# e3_ej5_esquematico.net
KiCad netlist of a schematic drawn in Altium Designer
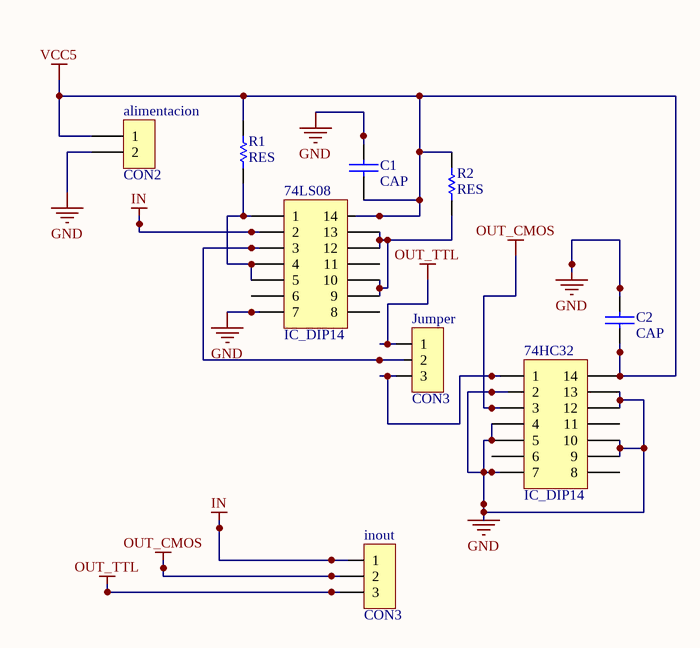
[diagram p0: e3_ej5_esquematico.SchDoc]

(export (version "E")
  (design (tool "Eeschema 10.0.6"))
  (components
    (comp (ref "74HC32") (value "IC_DIP14") (footprint "DIP14") (libsource (lib "LIBEBAL") (part "IC_DIP14")))
    (comp (ref "74LS08") (value "IC_DIP14") (footprint "DIP14") (libsource (lib "LIBEBAL") (part "IC_DIP14")))
    (comp (ref "alimentacion") (value "CON2") (footprint "SIP2") (libsource (lib "LIBEBAL") (part "CON2")))
    (comp (ref "C1") (value "CAP") (footprint "CAP200") (libsource (lib "LIBEBAL") (part "CAP")))
    (comp (ref "C2") (value "CAP") (footprint "CAP200") (libsource (lib "LIBEBAL") (part "CAP")))
    (comp (ref "inout") (value "CON3") (footprint "SIP3") (libsource (lib "LIBEBAL") (part "CON3")))
    (comp (ref "Jumper") (value "CON3") (footprint "SIP3") (libsource (lib "LIBEBAL") (part "CON3")))
    (comp (ref "R1") (value "RES") (footprint "RES300") (libsource (lib "LIBEBAL") (part "RES")))
    (comp (ref "R2") (value "RES") (footprint "RES300") (libsource (lib "LIBEBAL") (part "RES")))
  )
  (nets
    (net (code "1") (name "GND") (class "Default")
      (node (ref "74HC32") (pin "10") (pinfunction "10_10") (pintype "passive"))
      (node (ref "74HC32") (pin "12") (pinfunction "12_12") (pintype "passive"))
      (node (ref "74HC32") (pin "13") (pinfunction "13_13") (pintype "passive"))
      (node (ref "74HC32") (pin "2") (pinfunction "2_2") (pintype "passive"))
      (node (ref "74HC32") (pin "4") (pinfunction "4_4") (pintype "passive"))
      (node (ref "74HC32") (pin "5") (pinfunction "5_5") (pintype "passive"))
      (node (ref "74HC32") (pin "7") (pinfunction "7_7") (pintype "passive"))
      (node (ref "74HC32") (pin "9") (pinfunction "9_9") (pintype "passive"))
      (node (ref "74LS08") (pin "7") (pinfunction "7_7") (pintype "passive"))
      (node (ref "C1") (pin "1") (pinfunction "1_1") (pintype "passive"))
      (node (ref "C2") (pin "1") (pinfunction "1_1") (pintype "passive"))
      (node (ref "alimentacion") (pin "2") (pinfunction "2_2") (pintype "passive"))
    )
    (net (code "2") (name "IN") (class "Default")
      (node (ref "74LS08") (pin "2") (pinfunction "2_2") (pintype "passive"))
      (node (ref "inout") (pin "1") (pinfunction "1_1") (pintype "passive"))
    )
    (net (code "3") (name "Net-(74HC32-Pad1)") (class "Default")
      (node (ref "74HC32") (pin "1") (pinfunction "1_1") (pintype "passive"))
      (node (ref "Jumper") (pin "3") (pinfunction "3_3") (pintype "passive"))
    )
    (net (code "4") (name "Net-(74LS08-Pad1)") (class "Default")
      (node (ref "74LS08") (pin "1") (pinfunction "1_1") (pintype "passive"))
      (node (ref "74LS08") (pin "4") (pinfunction "4_4") (pintype "passive"))
      (node (ref "74LS08") (pin "5") (pinfunction "5_5") (pintype "passive"))
      (node (ref "R1") (pin "1") (pinfunction "1_1") (pintype "passive"))
    )
    (net (code "5") (name "Net-(74LS08-Pad3)") (class "Default")
      (node (ref "74LS08") (pin "3") (pinfunction "3_3") (pintype "passive"))
      (node (ref "Jumper") (pin "2") (pinfunction "2_2") (pintype "passive"))
    )
    (net (code "6") (name "Net-(74LS08-Pad10)") (class "Default")
      (node (ref "74LS08") (pin "10") (pinfunction "10_10") (pintype "passive"))
      (node (ref "74LS08") (pin "12") (pinfunction "12_12") (pintype "passive"))
      (node (ref "74LS08") (pin "13") (pinfunction "13_13") (pintype "passive"))
      (node (ref "74LS08") (pin "9") (pinfunction "9_9") (pintype "passive"))
      (node (ref "R2") (pin "1") (pinfunction "1_1") (pintype "passive"))
    )
    (net (code "7") (name "OUT_CMOS") (class "Default")
      (node (ref "74HC32") (pin "3") (pinfunction "3_3") (pintype "passive"))
      (node (ref "inout") (pin "2") (pinfunction "2_2") (pintype "passive"))
    )
    (net (code "8") (name "OUT_TTL") (class "Default")
      (node (ref "Jumper") (pin "1") (pinfunction "1_1") (pintype "passive"))
      (node (ref "inout") (pin "3") (pinfunction "3_3") (pintype "passive"))
    )
    (net (code "9") (name "VCC5") (class "Default")
      (node (ref "74HC32") (pin "14") (pinfunction "14_14") (pintype "passive"))
      (node (ref "74LS08") (pin "14") (pinfunction "14_14") (pintype "passive"))
      (node (ref "C1") (pin "2") (pinfunction "2_2") (pintype "passive"))
      (node (ref "C2") (pin "2") (pinfunction "2_2") (pintype "passive"))
      (node (ref "R1") (pin "2") (pinfunction "2_2") (pintype "passive"))
      (node (ref "R2") (pin "2") (pinfunction "2_2") (pintype "passive"))
      (node (ref "alimentacion") (pin "1") (pinfunction "1_1") (pintype "passive"))
    )
    (net (code "10") (name "unconnected-(74HC32-Pad6)") (class "Default")
      (node (ref "74HC32") (pin "6") (pinfunction "6_6") (pintype "passive"))
    )
    (net (code "11") (name "unconnected-(74HC32-Pad8)") (class "Default")
      (node (ref "74HC32") (pin "8") (pinfunction "8_8") (pintype "passive"))
    )
    (net (code "12") (name "unconnected-(74HC32-Pad11)") (class "Default")
      (node (ref "74HC32") (pin "11") (pinfunction "11_11") (pintype "passive"))
    )
    (net (code "13") (name "unconnected-(74LS08-Pad6)") (class "Default")
      (node (ref "74LS08") (pin "6") (pinfunction "6_6") (pintype "passive"))
    )
    (net (code "14") (name "unconnected-(74LS08-Pad8)") (class "Default")
      (node (ref "74LS08") (pin "8") (pinfunction "8_8") (pintype "passive"))
    )
    (net (code "15") (name "unconnected-(74LS08-Pad11)") (class "Default")
      (node (ref "74LS08") (pin "11") (pinfunction "11_11") (pintype "passive"))
    )
  )
)
